# ultrasonic-test.net
KiCad netlist of a schematic drawn in EAGLE
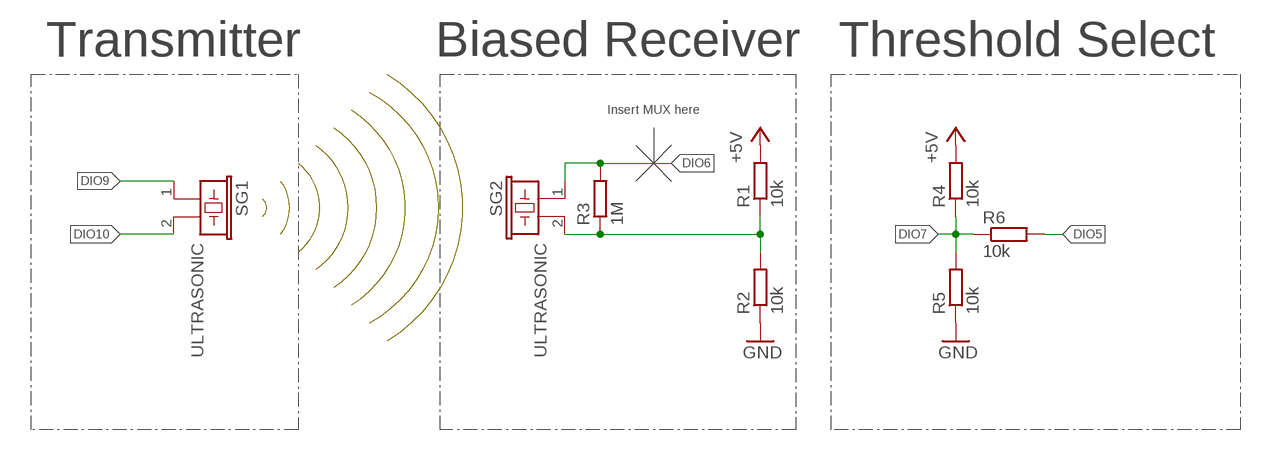
[diagram p0: schematic, sheet 1]

(export (version "E")
  (design (tool "Eeschema 10.0.6"))
  (components
    (comp (ref "R1")
      (value "10k")
      (footprint "eagle-import:R0402")
      (libsource (lib "eagle-import") (part "R-EU_R0402"))
    )
    (comp (ref "R2")
      (value "10k")
      (footprint "eagle-import:R0402")
      (libsource (lib "eagle-import") (part "R-EU_R0402"))
    )
    (comp (ref "R3")
      (value "1M")
      (footprint "eagle-import:R0402")
      (libsource (lib "eagle-import") (part "R-EU_R0402"))
    )
    (comp (ref "R4")
      (value "10k")
      (footprint "eagle-import:R0402")
      (libsource (lib "eagle-import") (part "R-EU_R0402"))
    )
    (comp (ref "R5")
      (value "10k")
      (footprint "eagle-import:R0402")
      (libsource (lib "eagle-import") (part "R-EU_R0402"))
    )
    (comp (ref "R6")
      (value "10k")
      (footprint "eagle-import:R0402")
      (libsource (lib "eagle-import") (part "R-EU_R0402"))
    )
    (comp (ref "SG1")
      (value "ULTRASONIC")
      (footprint "eagle-import:EFBAA40D101")
      (libsource (lib "eagle-import") (part "EFB?AA40D101"))
    )
    (comp (ref "SG2")
      (value "ULTRASONIC")
      (footprint "eagle-import:EFBAA40D101")
      (libsource (lib "eagle-import") (part "EFB?AA40D101"))
    )
  )
  (nets
    (net (code "1") (name "+5V") (class "Default")
      (node (ref "R1") (pin "2") (pinfunction "2_2") (pintype "passive"))
      (node (ref "R4") (pin "2") (pinfunction "2_2") (pintype "passive"))
    )
    (net (code "2") (name "DIO5") (class "Default")
      (node (ref "R6") (pin "2") (pinfunction "2_2") (pintype "passive"))
    )
    (net (code "3") (name "DIO6") (class "Default")
      (node (ref "R3") (pin "2") (pinfunction "2_2") (pintype "passive"))
      (node (ref "SG2") (pin "1") (pinfunction "1_1") (pintype "passive"))
    )
    (net (code "4") (name "DIO7") (class "Default")
      (node (ref "R4") (pin "1") (pinfunction "1_1") (pintype "passive"))
      (node (ref "R5") (pin "2") (pinfunction "2_2") (pintype "passive"))
      (node (ref "R6") (pin "1") (pinfunction "1_1") (pintype "passive"))
    )
    (net (code "5") (name "DIO9") (class "Default")
      (node (ref "SG1") (pin "1") (pinfunction "1_1") (pintype "passive"))
    )
    (net (code "6") (name "DIO10") (class "Default")
      (node (ref "SG1") (pin "2") (pinfunction "2_2") (pintype "passive"))
    )
    (net (code "7") (name "GND") (class "Default")
      (node (ref "R2") (pin "1") (pinfunction "1_1") (pintype "passive"))
      (node (ref "R5") (pin "1") (pinfunction "1_1") (pintype "passive"))
    )
    (net (code "8") (name "Net-(R1-Pad1)") (class "Default")
      (node (ref "R1") (pin "1") (pinfunction "1_1") (pintype "passive"))
      (node (ref "R2") (pin "2") (pinfunction "2_2") (pintype "passive"))
      (node (ref "R3") (pin "1") (pinfunction "1_1") (pintype "passive"))
      (node (ref "SG2") (pin "2") (pinfunction "2_2") (pintype "passive"))
    )
  )
)
